# controller_board.net
KiCad netlist of a schematic drawn in EAGLE
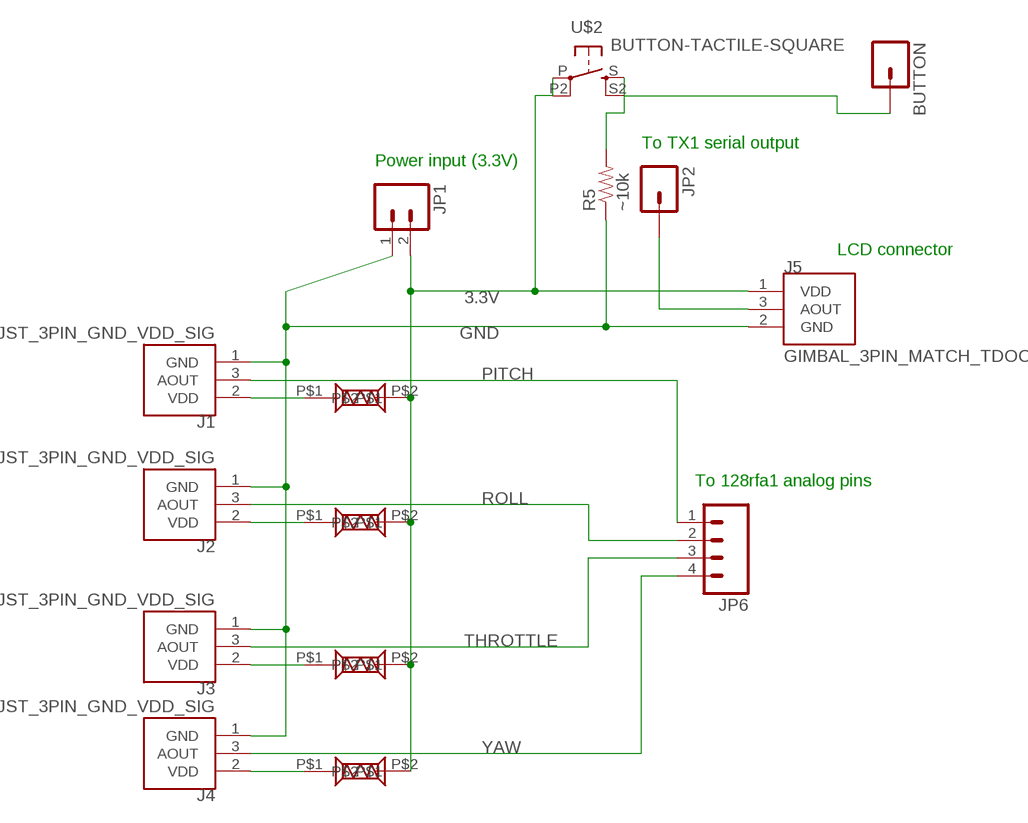
[diagram p0: schematic, sheet 1]

(export (version "E")
  (design (tool "Eeschema 10.0.6"))
  (components
    (comp (ref "BUTTON")
      (value "M01PTH")
      (footprint "eagle-import:1X01")
      (libsource (lib "eagle-import") (part "M01PTH"))
    )
    (comp (ref "J1")
      (value "JST_3PIN_GND_VDD_SIG")
      (footprint "eagle-import:JST-3-PTH-REVERSE")
      (libsource (lib "eagle-import") (part "JST_3PIN_GND_VDD_SIG"))
    )
    (comp (ref "J2")
      (value "JST_3PIN_GND_VDD_SIG")
      (footprint "eagle-import:JST-3-PTH-REVERSE")
      (libsource (lib "eagle-import") (part "JST_3PIN_GND_VDD_SIG"))
    )
    (comp (ref "J3")
      (value "JST_3PIN_GND_VDD_SIG")
      (footprint "eagle-import:JST-3-PTH-REVERSE")
      (libsource (lib "eagle-import") (part "JST_3PIN_GND_VDD_SIG"))
    )
    (comp (ref "J4")
      (value "JST_3PIN_GND_VDD_SIG")
      (footprint "eagle-import:JST-3-PTH-REVERSE")
      (libsource (lib "eagle-import") (part "JST_3PIN_GND_VDD_SIG"))
    )
    (comp (ref "J5")
      (value "GIMBAL_3PIN_MATCH_TDOCU")
      (footprint "eagle-import:JST-3-PTH")
      (libsource (lib "eagle-import") (part "GIMBAL_3PIN_MATCH_TDOCU"))
    )
    (comp (ref "JP1")
      (value "M021X02_NO_SILK")
      (footprint "eagle-import:1X02_NO_SILK")
      (libsource (lib "eagle-import") (part "M021X02_NO_SILK"))
    )
    (comp (ref "JP2")
      (value "M01PTH")
      (footprint "eagle-import:1X01")
      (libsource (lib "eagle-import") (part "M01PTH"))
    )
    (comp (ref "JP6")
      (value "M04PTH")
      (footprint "eagle-import:1X04")
      (libsource (lib "eagle-import") (part "M04PTH"))
    )
    (comp (ref "R")
      (value "4k")
      (footprint "eagle-import:CRF12_RESISTOR")
      (libsource (lib "eagle-import") (part "CRF12_RESISTOR"))
    )
    (comp (ref "R2")
      (value "2k")
      (footprint "eagle-import:CRF12_RESISTOR")
      (libsource (lib "eagle-import") (part "CRF12_RESISTOR"))
    )
    (comp (ref "R3")
      (value "4k")
      (footprint "eagle-import:CRF12_RESISTOR")
      (libsource (lib "eagle-import") (part "CRF12_RESISTOR"))
    )
    (comp (ref "R4")
      (value "2k")
      (footprint "eagle-import:CRF12_RESISTOR")
      (libsource (lib "eagle-import") (part "CRF12_RESISTOR"))
    )
    (comp (ref "R5")
      (value "~10k")
      (footprint "eagle-import:AXIAL-0.4")
      (libsource (lib "eagle-import") (part "RESISTORPTH-1/4W"))
    )
    (comp (ref "U$2")
      (value "BUTTON-TACTILE-SQUARE")
      (footprint "eagle-import:BUTTON-TACTILE-SQUARE-ADAFRUIT1010")
      (libsource (lib "eagle-import") (part "BUTTON-TACTILE-SQUARE"))
    )
  )
  (nets
    (net (code "1") (name "/3.3V") (class "Default")
      (node (ref "J5") (pin "1") (pinfunction "VDD_1") (pintype "power_in"))
      (node (ref "JP1") (pin "2") (pinfunction "2_2") (pintype "passive"))
      (node (ref "R") (pin "P$2") (pinfunction "P$2_P$2") (pintype "bidirectional"))
      (node (ref "R2") (pin "P$2") (pinfunction "P$2_P$2") (pintype "bidirectional"))
      (node (ref "R3") (pin "P$2") (pinfunction "P$2_P$2") (pintype "bidirectional"))
      (node (ref "R4") (pin "P$2") (pinfunction "P$2_P$2") (pintype "bidirectional"))
      (node (ref "U$2") (pin "P") (pinfunction "P_P") (pintype "passive"))
      (node (ref "U$2") (pin "P2") (pinfunction "P1_P2") (pintype "passive"))
    )
    (net (code "2") (name "/GND") (class "Default")
      (node (ref "J1") (pin "1") (pinfunction "GND_1") (pintype "power_in"))
      (node (ref "J2") (pin "1") (pinfunction "GND_1") (pintype "power_in"))
      (node (ref "J3") (pin "1") (pinfunction "GND_1") (pintype "power_in"))
      (node (ref "J4") (pin "1") (pinfunction "GND_1") (pintype "power_in"))
      (node (ref "J5") (pin "2") (pinfunction "GND_2") (pintype "power_in"))
      (node (ref "JP1") (pin "1") (pinfunction "1_1") (pintype "passive"))
      (node (ref "R5") (pin "P$1") (pinfunction "1_P$1") (pintype "passive"))
    )
    (net (code "3") (name "/PITCH") (class "Default")
      (node (ref "J1") (pin "3") (pinfunction "AOUT_3") (pintype "bidirectional"))
      (node (ref "JP6") (pin "1") (pinfunction "1_1") (pintype "passive"))
    )
    (net (code "4") (name "/ROLL") (class "Default")
      (node (ref "J2") (pin "3") (pinfunction "AOUT_3") (pintype "bidirectional"))
      (node (ref "JP6") (pin "2") (pinfunction "2_2") (pintype "passive"))
    )
    (net (code "5") (name "/THROTTLE") (class "Default")
      (node (ref "J3") (pin "3") (pinfunction "AOUT_3") (pintype "bidirectional"))
      (node (ref "JP6") (pin "3") (pinfunction "3_3") (pintype "passive"))
    )
    (net (code "6") (name "/YAW") (class "Default")
      (node (ref "J4") (pin "3") (pinfunction "AOUT_3") (pintype "bidirectional"))
      (node (ref "JP6") (pin "4") (pinfunction "4_4") (pintype "passive"))
    )
    (net (code "7") (name "Net-(J1-VDD)") (class "Default")
      (node (ref "J1") (pin "2") (pinfunction "VDD_2") (pintype "power_in"))
      (node (ref "R") (pin "P$1") (pinfunction "P$1_P$1") (pintype "bidirectional"))
    )
    (net (code "8") (name "Net-(J2-VDD)") (class "Default")
      (node (ref "J2") (pin "2") (pinfunction "VDD_2") (pintype "power_in"))
      (node (ref "R2") (pin "P$1") (pinfunction "P$1_P$1") (pintype "bidirectional"))
    )
    (net (code "9") (name "Net-(J3-VDD)") (class "Default")
      (node (ref "J3") (pin "2") (pinfunction "VDD_2") (pintype "power_in"))
      (node (ref "R3") (pin "P$1") (pinfunction "P$1_P$1") (pintype "bidirectional"))
    )
    (net (code "10") (name "Net-(J4-VDD)") (class "Default")
      (node (ref "J4") (pin "2") (pinfunction "VDD_2") (pintype "power_in"))
      (node (ref "R4") (pin "P$1") (pinfunction "P$1_P$1") (pintype "bidirectional"))
    )
    (net (code "11") (name "Net-(J5-AOUT)") (class "Default")
      (node (ref "J5") (pin "3") (pinfunction "AOUT_3") (pintype "bidirectional"))
      (node (ref "JP2") (pin "1") (pinfunction "1_1") (pintype "passive"))
    )
    (net (code "12") (name "Net-(R5-2)") (class "Default")
      (node (ref "BUTTON") (pin "1") (pinfunction "1_1") (pintype "passive"))
      (node (ref "R5") (pin "P$2") (pinfunction "2_P$2") (pintype "passive"))
      (node (ref "U$2") (pin "S") (pinfunction "S_S") (pintype "passive"))
      (node (ref "U$2") (pin "S2") (pinfunction "S1_S2") (pintype "passive"))
    )
  )
)
